# Differential_Encoder_Receiver.net
KiCad netlist of a schematic drawn in Altium Designer
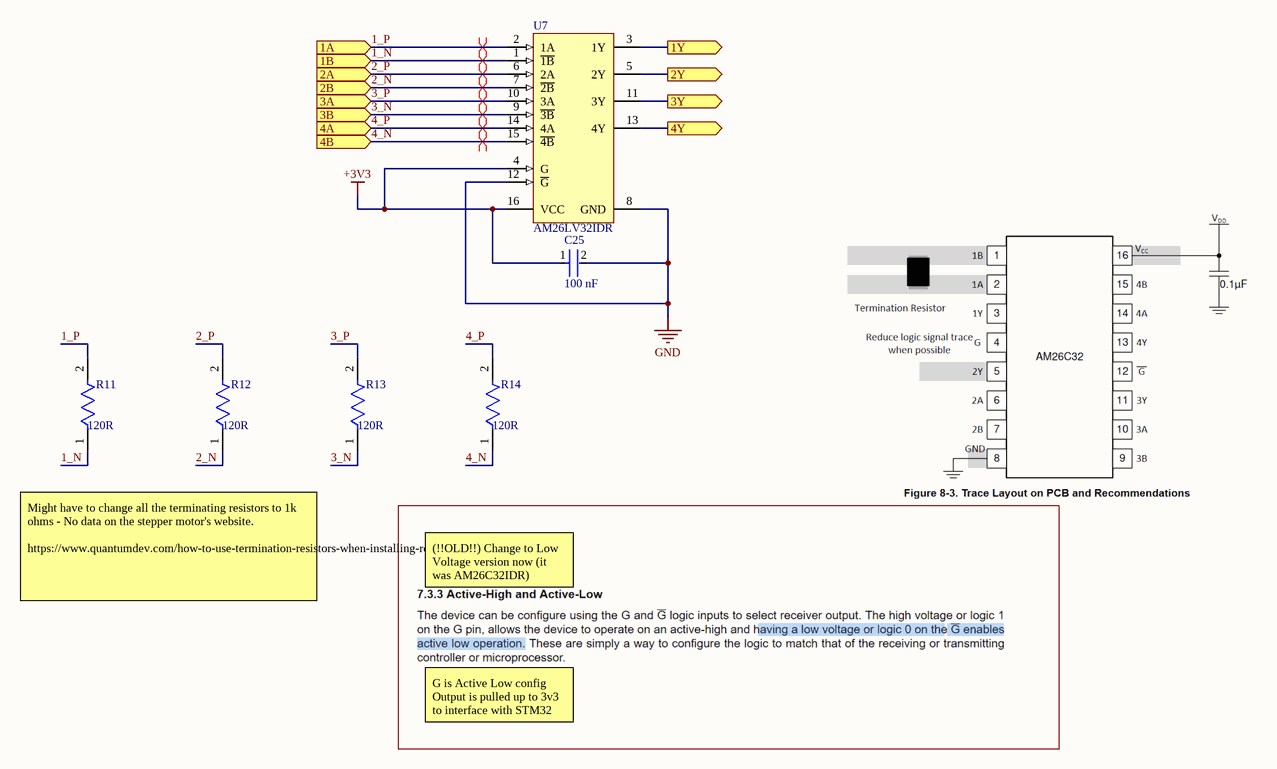
[diagram p0: Differential Encoder Receiver.SchDoc]

(export (version "E")
  (design (tool "Eeschema 10.0.6"))
  (components
    (comp (ref "C25")
      (value "CC0603KRX7R9BB104")
      (footprint "FP-CC0603-DA-MFG")
      (description "CAP CER 0.1UF 50V X7R 0603")
      (fields
        (field (name "MANUFACTURER") "YAGEO")
        (field (name "VOLTAGE") "50 V")
        (field (name "CAPACITANCE") "100 nF")
      )
      (libsource (lib "Altium Content Vault") (part "11868f565c42a9108669ba33697ecf6"))
    )
    (comp (ref "R11")
      (value "0603WAF1200T5E")
      (footprint "FP-CRCW0603-e3-MFG")
      (description "100mW Thick Film Resistors 75V ±100ppm/℃ ±1% 120Ω 0603 Chip Resistor - Surface Mount ROHS")
      (fields (field (name "TOLERANCE") "1%") (field (name "RESISTANCE") "120R"))
      (libsource (lib "Altium Content Vault") (part "1029c3af85768c4190bb7ad29bc67b5"))
    )
    (comp (ref "R12")
      (value "0603WAF1200T5E")
      (footprint "FP-CRCW0603-e3-MFG")
      (description "100mW Thick Film Resistors 75V ±100ppm/℃ ±1% 120Ω 0603 Chip Resistor - Surface Mount ROHS")
      (fields (field (name "TOLERANCE") "1%") (field (name "RESISTANCE") "120R"))
      (libsource (lib "Altium Content Vault") (part "1029c3af85768c4190bb7ad29bc67b5"))
    )
    (comp (ref "R13")
      (value "0603WAF1200T5E")
      (footprint "FP-CRCW0603-e3-MFG")
      (description "100mW Thick Film Resistors 75V ±100ppm/℃ ±1% 120Ω 0603 Chip Resistor - Surface Mount ROHS")
      (fields (field (name "TOLERANCE") "1%") (field (name "RESISTANCE") "120R"))
      (libsource (lib "Altium Content Vault") (part "1029c3af85768c4190bb7ad29bc67b5"))
    )
    (comp (ref "R14")
      (value "0603WAF1200T5E")
      (footprint "FP-CRCW0603-e3-MFG")
      (description "100mW Thick Film Resistors 75V ±100ppm/℃ ±1% 120Ω 0603 Chip Resistor - Surface Mount ROHS")
      (fields (field (name "TOLERANCE") "1%") (field (name "RESISTANCE") "120R"))
      (libsource (lib "Altium Content Vault") (part "1029c3af85768c4190bb7ad29bc67b5"))
    )
    (comp (ref "U7")
      (value "AM26LV32IDR")
      (footprint "D0016A_N")
      (fields (field (name "MANUFACTURER") "Texas Instruments"))
      (libsource (lib "Altium Content Vault") (part "TI-AM26LV32-SOIC_D-16"))
    )
  )
  (nets
    (net (code "1") (name "+3V3") (class "Default")
      (node (ref "C25") (pin "1") (pinfunction "1_1") (pintype "passive"))
      (node (ref "U7") (pin "16") (pinfunction "VCC_16") (pintype "power_in"))
      (node (ref "U7") (pin "4") (pinfunction "G_4") (pintype "input"))
    )
    (net (code "2") (name "/1Y") (class "Default")
      (node (ref "U7") (pin "3") (pinfunction "1Y_3") (pintype "tri_state"))
    )
    (net (code "3") (name "/1_N") (class "Default")
      (node (ref "R11") (pin "1") (pinfunction "1_1") (pintype "passive"))
      (node (ref "U7") (pin "1") (pinfunction "~{1B}_1") (pintype "input"))
    )
    (net (code "4") (name "/1_P") (class "Default")
      (node (ref "R11") (pin "2") (pinfunction "2_2") (pintype "passive"))
      (node (ref "U7") (pin "2") (pinfunction "1A_2") (pintype "input"))
    )
    (net (code "5") (name "/2Y") (class "Default")
      (node (ref "U7") (pin "5") (pinfunction "2Y_5") (pintype "tri_state"))
    )
    (net (code "6") (name "/2_N") (class "Default")
      (node (ref "R12") (pin "1") (pinfunction "1_1") (pintype "passive"))
      (node (ref "U7") (pin "7") (pinfunction "~{2B}_7") (pintype "input"))
    )
    (net (code "7") (name "/2_P") (class "Default")
      (node (ref "R12") (pin "2") (pinfunction "2_2") (pintype "passive"))
      (node (ref "U7") (pin "6") (pinfunction "2A_6") (pintype "input"))
    )
    (net (code "8") (name "/3Y") (class "Default")
      (node (ref "U7") (pin "11") (pinfunction "3Y_11") (pintype "tri_state"))
    )
    (net (code "9") (name "/3_N") (class "Default")
      (node (ref "R13") (pin "1") (pinfunction "1_1") (pintype "passive"))
      (node (ref "U7") (pin "9") (pinfunction "~{3B}_9") (pintype "input"))
    )
    (net (code "10") (name "/3_P") (class "Default")
      (node (ref "R13") (pin "2") (pinfunction "2_2") (pintype "passive"))
      (node (ref "U7") (pin "10") (pinfunction "3A_10") (pintype "input"))
    )
    (net (code "11") (name "/4Y") (class "Default")
      (node (ref "U7") (pin "13") (pinfunction "4Y_13") (pintype "tri_state"))
    )
    (net (code "12") (name "/4_N") (class "Default")
      (node (ref "R14") (pin "1") (pinfunction "1_1") (pintype "passive"))
      (node (ref "U7") (pin "15") (pinfunction "~{4B}_15") (pintype "input"))
    )
    (net (code "13") (name "/4_P") (class "Default")
      (node (ref "R14") (pin "2") (pinfunction "2_2") (pintype "passive"))
      (node (ref "U7") (pin "14") (pinfunction "4A_14") (pintype "input"))
    )
    (net (code "14") (name "GND") (class "Default")
      (node (ref "C25") (pin "2") (pinfunction "2_2") (pintype "passive"))
      (node (ref "U7") (pin "12") (pinfunction "~{G}_12") (pintype "input"))
      (node (ref "U7") (pin "8") (pinfunction "GND_8") (pintype "power_in"))
    )
  )
)
